# Sheet1.net
KiCad netlist of a schematic drawn in Altium Designer
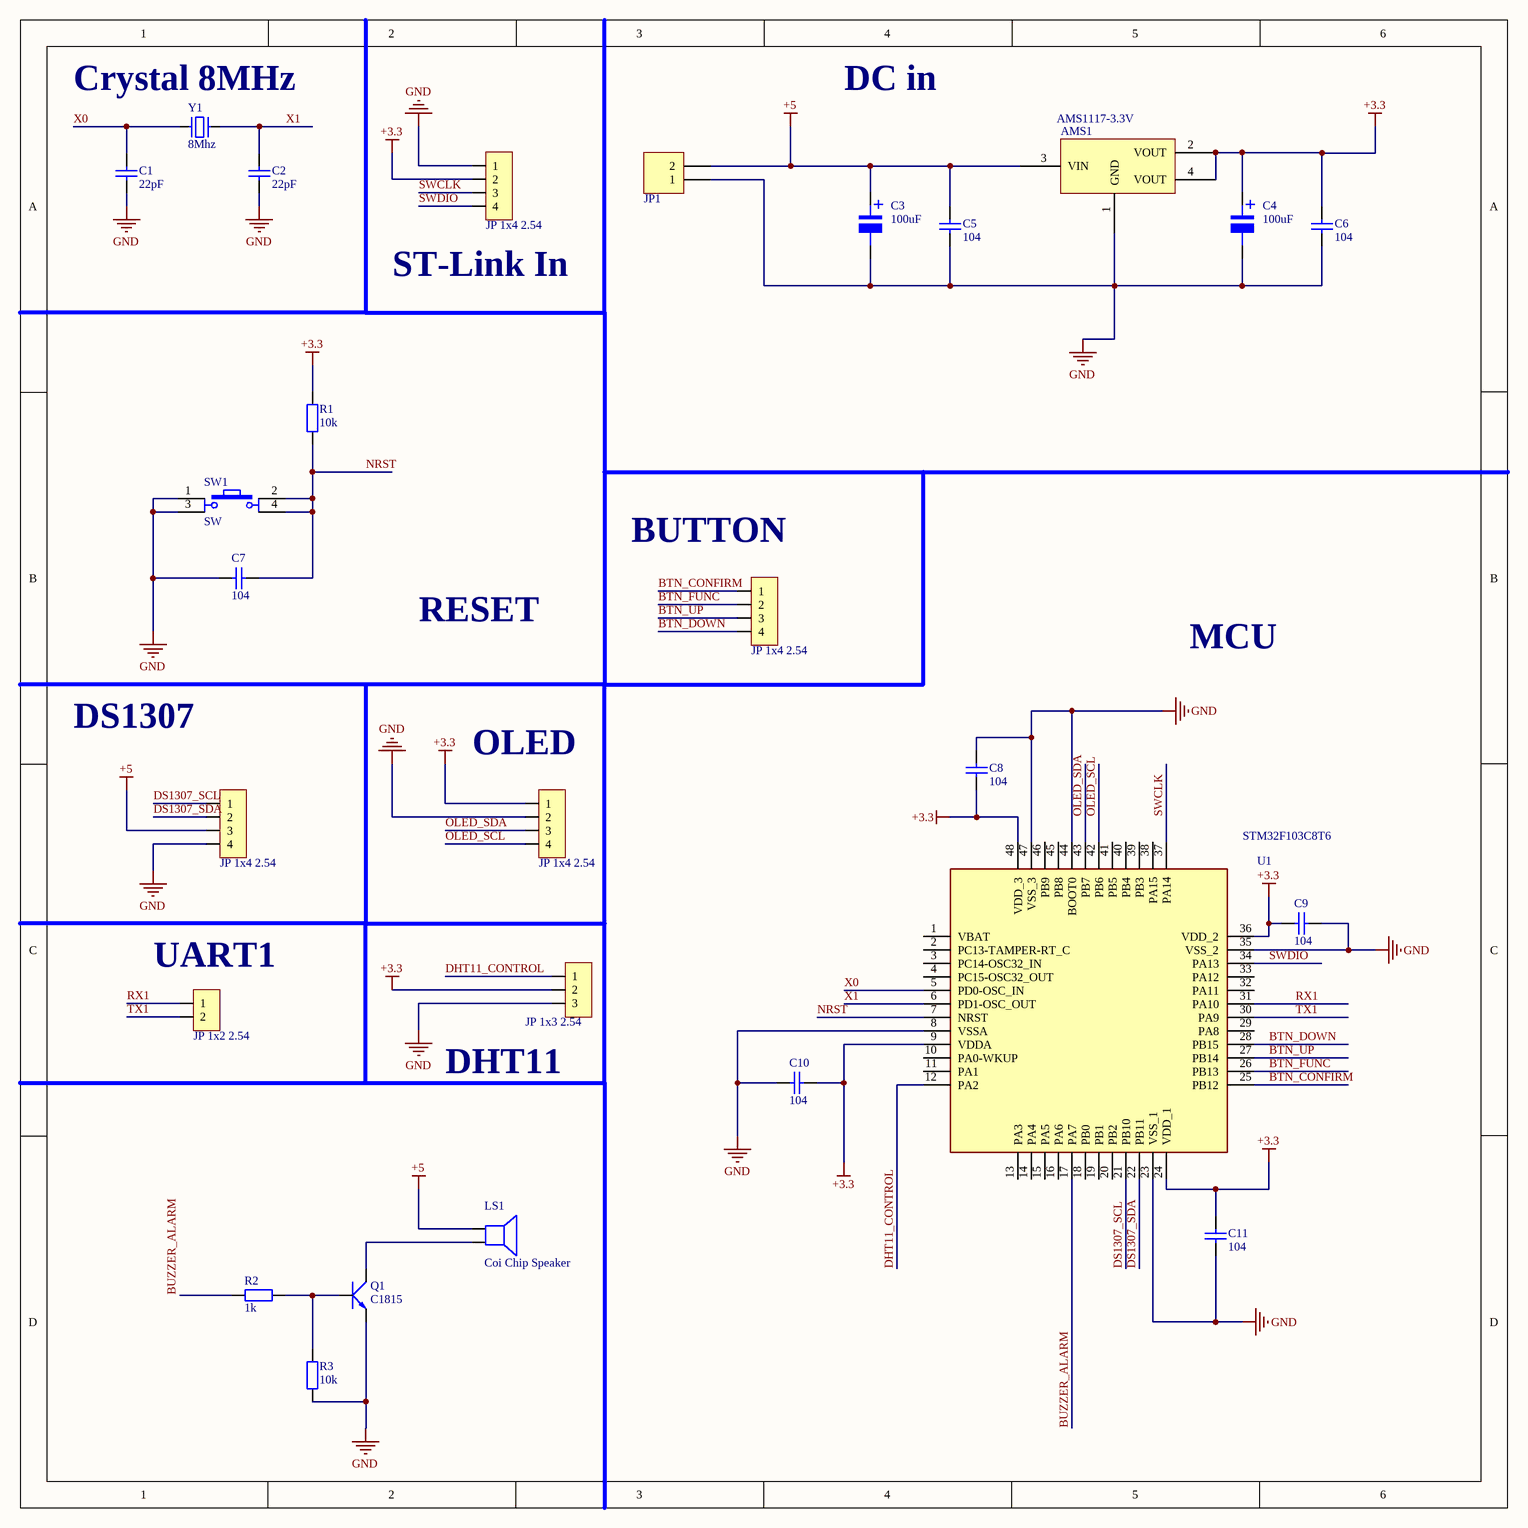
[diagram p0: Sheet1.SchDoc]

(export (version "E")
  (design (tool "Eeschema 10.0.6"))
  (components
    (comp (ref "AMS1")
      (value "AMS1117-3.3V")
      (footprint "SOT223")
      (description "Dán")
      (libsource (lib "Altium_Lib_by_KhueNguyenCreator") (part "AMS1117 SMD"))
    )
    (comp (ref "C1")
      (value "22pF")
      (footprint "tu 1206")
      (description "Dán")
      (libsource (lib "Altium_Lib_by_KhueNguyenCreator") (part "Tu 1206 22pF 50V 10%"))
    )
    (comp (ref "C2")
      (value "22pF")
      (footprint "tu 1206")
      (description "Dán")
      (libsource (lib "Altium_Lib_by_KhueNguyenCreator") (part "Tu 1206 22pF 50V 10%"))
    )
    (comp (ref "C3")
      (value "100uF")
      (footprint "tu nhom 6.3 (d)")
      (description "Dán")
      (libsource (lib "Altium_Lib_by_KhueNguyenCreator") (part "Tu Nhom 100uF 16V"))
    )
    (comp (ref "C4")
      (value "100uF")
      (footprint "tu nhom 6.3 (d)")
      (description "Dán")
      (libsource (lib "Altium_Lib_by_KhueNguyenCreator") (part "Tu Nhom 100uF 16V"))
    )
    (comp (ref "C5")
      (value "104")
      (footprint "tu 1206")
      (description "Dán")
      (libsource (lib "Altium_Lib_by_KhueNguyenCreator") (part "Tu 1206 104 50V 20%"))
    )
    (comp (ref "C6")
      (value "104")
      (footprint "tu 1206")
      (description "Dán")
      (libsource (lib "Altium_Lib_by_KhueNguyenCreator") (part "Tu 1206 104 50V 20%"))
    )
    (comp (ref "C7")
      (value "104")
      (footprint "tu 1206")
      (description "Dán")
      (libsource (lib "Altium_Lib_by_KhueNguyenCreator") (part "Tu 1206 104 50V 20%"))
    )
    (comp (ref "C8")
      (value "104")
      (footprint "tu 1206")
      (description "Dán")
      (libsource (lib "Altium_Lib_by_KhueNguyenCreator") (part "Tu 1206 104 50V 20%"))
    )
    (comp (ref "C9")
      (value "104")
      (footprint "tu 1206")
      (description "Dán")
      (libsource (lib "Altium_Lib_by_KhueNguyenCreator") (part "Tu 1206 104 50V 20%"))
    )
    (comp (ref "C10")
      (value "104")
      (footprint "tu 1206")
      (description "Dán")
      (libsource (lib "Altium_Lib_by_KhueNguyenCreator") (part "Tu 1206 104 50V 20%"))
    )
    (comp (ref "C11")
      (value "104")
      (footprint "tu 1206")
      (description "Dán")
      (libsource (lib "Altium_Lib_by_KhueNguyenCreator") (part "Tu 1206 104 50V 20%"))
    )
    (comp (ref "JP1")
      (value "Header 2_1")
      (footprint "HED2")
      (description "Header, 2-Pin")
      (fields (field (name "MANUFACTURER") "Generic Components"))
      (libsource (lib "syhaunguyen") (part "Header 2_1"))
    )
    (comp (ref "JP2")
      (value "JP 1x4 2.54")
      (footprint "JP 1x4 DT")
      (description "Cắm")
      (libsource (lib "Altium_Lib_by_KhueNguyenCreator") (part "JP 1x4 2.54 Duc Thang"))
    )
    (comp (ref "JP3")
      (value "JP 1x4 2.54")
      (footprint "JP 1x4 DT")
      (description "Cắm")
      (libsource (lib "Altium_Lib_by_KhueNguyenCreator") (part "JP 1x4 2.54 Duc Thang"))
    )
    (comp (ref "JP4")
      (value "JP 1x4 2.54")
      (footprint "JP 1x4 DT")
      (description "Cắm")
      (libsource (lib "Altium_Lib_by_KhueNguyenCreator") (part "JP 1x4 2.54 Duc Thang"))
    )
    (comp (ref "JP5")
      (value "JP 1x4 2.54")
      (footprint "JP 1x4 DT")
      (description "Cắm")
      (libsource (lib "Altium_Lib_by_KhueNguyenCreator") (part "JP 1x4 2.54 Duc Thang"))
    )
    (comp (ref "JP6")
      (value "JP 1x3 2.54")
      (footprint "JP 1x3 DT")
      (description "Cắm")
      (libsource (lib "Altium_Lib_by_KhueNguyenCreator") (part "JP 1x3 2.54 Duc Thang"))
    )
    (comp (ref "JP7")
      (value "JP 1x2 2.54")
      (footprint "JP 1x2 DT")
      (description "Cắm")
      (libsource (lib "Altium_Lib_by_KhueNguyenCreator") (part "JP 1x2 2.54 Duc Thang"))
    )
    (comp (ref "LS1")
      (value "Coi Chip Speaker")
      (footprint "Coi Chip Speacker")
      (description "Còi chip")
      (libsource (lib "Altium_Lib_by_KhueNguyenCreator") (part "Coi Chip Speaker"))
    )
    (comp (ref "Q1")
      (value "C1815")
      (footprint "TO92")
      (description "NPN transistor")
      (libsource (lib "Altium_Lib_by_KhueNguyenCreator") (part "Trans C1815 DIP"))
    )
    (comp (ref "R1")
      (value "10k")
      (footprint "tro smd 1206")
      (description "Dán")
      (libsource (lib "Altium_Lib_by_KhueNguyenCreator") (part "Tro 1206 1% 10k"))
    )
    (comp (ref "R2")
      (value "1k")
      (footprint "tro smd 1206")
      (description "Dán")
      (libsource (lib "Altium_Lib_by_KhueNguyenCreator") (part "Tro 1206 1% 1k"))
    )
    (comp (ref "R3")
      (value "10k")
      (footprint "tro smd 1206")
      (description "Dán")
      (libsource (lib "Altium_Lib_by_KhueNguyenCreator") (part "Tro 1206 1% 10k"))
    )
    (comp (ref "SW1")
      (value "SW")
      (footprint "SW4")
      (description "Switch button 4 pin")
      (libsource (lib "syhaunguyen") (part "SW4"))
    )
    (comp (ref "U1")
      (value "STM32F103C8T6")
      (footprint "LQFP-48_19.6_393_58X11_SMD")
      (description "ARM® Cortex®-M3 STM32F1 Microcontroller IC 32-Bit 72MHz 64KB (64K x 8) FLASH 48-LQFP (7x7)")
      (fields (field (name "MANUFACTURER") "STMicroelectronics"))
      (libsource (lib "Altium_Lib_by_KhueNguyenCreator") (part "IC_STM32F103C8T6"))
    )
    (comp (ref "Y1")
      (value "8Mhz")
      (footprint "Thach Anh 2 chan SMD")
      (description "Crystal For all Crystal 2pin.")
      (libsource (lib "Altium_Lib_by_KhueNguyenCreator") (part "Thach Anh 2 chan SMD"))
    )
  )
  (nets
    (net (code "1") (name "+3.3") (class "Default")
      (node (ref "AMS1") (pin "2") (pinfunction "VOUT_2") (pintype "passive"))
      (node (ref "AMS1") (pin "4") (pinfunction "VOUT_4") (pintype "passive"))
      (node (ref "C10") (pin "1") (pinfunction "1_1") (pintype "passive"))
      (node (ref "C11") (pin "1") (pinfunction "1_1") (pintype "passive"))
      (node (ref "C4") (pin "1") (pinfunction "1_1") (pintype "passive"))
      (node (ref "C6") (pin "1") (pinfunction "1_1") (pintype "passive"))
      (node (ref "C8") (pin "2") (pinfunction "2_2") (pintype "passive"))
      (node (ref "C9") (pin "2") (pinfunction "2_2") (pintype "passive"))
      (node (ref "JP2") (pin "2") (pinfunction "2_2") (pintype "passive"))
      (node (ref "JP5") (pin "1") (pinfunction "1_1") (pintype "passive"))
      (node (ref "JP6") (pin "2") (pinfunction "2_2") (pintype "passive"))
      (node (ref "R1") (pin "2") (pinfunction "2_2") (pintype "passive"))
      (node (ref "U1") (pin "24") (pinfunction "VDD_1_24") (pintype "passive"))
      (node (ref "U1") (pin "36") (pinfunction "VDD_2_36") (pintype "passive"))
      (node (ref "U1") (pin "48") (pinfunction "VDD_3_48") (pintype "passive"))
      (node (ref "U1") (pin "9") (pinfunction "VDDA_9") (pintype "passive"))
    )
    (net (code "2") (name "+5") (class "Default")
      (node (ref "AMS1") (pin "3") (pinfunction "VIN_3") (pintype "passive"))
      (node (ref "C3") (pin "1") (pinfunction "1_1") (pintype "passive"))
      (node (ref "C5") (pin "1") (pinfunction "1_1") (pintype "passive"))
      (node (ref "JP1") (pin "2") (pinfunction "2_2") (pintype "passive"))
      (node (ref "JP4") (pin "3") (pinfunction "3_3") (pintype "passive"))
      (node (ref "LS1") (pin "1") (pinfunction "1_1") (pintype "passive"))
    )
    (net (code "3") (name "/BTN_CONFIRM") (class "Default")
      (node (ref "JP3") (pin "1") (pinfunction "1_1") (pintype "passive"))
      (node (ref "U1") (pin "25") (pinfunction "PB12_25") (pintype "passive"))
    )
    (net (code "4") (name "/BTN_DOWN") (class "Default")
      (node (ref "JP3") (pin "4") (pinfunction "4_4") (pintype "passive"))
      (node (ref "U1") (pin "28") (pinfunction "PB15_28") (pintype "passive"))
    )
    (net (code "5") (name "/BTN_FUNC") (class "Default")
      (node (ref "JP3") (pin "2") (pinfunction "2_2") (pintype "passive"))
      (node (ref "U1") (pin "26") (pinfunction "PB13_26") (pintype "passive"))
    )
    (net (code "6") (name "/BTN_UP") (class "Default")
      (node (ref "JP3") (pin "3") (pinfunction "3_3") (pintype "passive"))
      (node (ref "U1") (pin "27") (pinfunction "PB14_27") (pintype "passive"))
    )
    (net (code "7") (name "/BUZZER_ALARM") (class "Default")
      (node (ref "R2") (pin "1") (pinfunction "1_1") (pintype "passive"))
      (node (ref "U1") (pin "17") (pinfunction "PA7_17") (pintype "passive"))
    )
    (net (code "8") (name "/DHT11_CONTROL") (class "Default")
      (node (ref "JP6") (pin "1") (pinfunction "1_1") (pintype "passive"))
      (node (ref "U1") (pin "12") (pinfunction "PA2_12") (pintype "passive"))
    )
    (net (code "9") (name "/DS1307_SCL") (class "Default")
      (node (ref "JP4") (pin "1") (pinfunction "1_1") (pintype "passive"))
      (node (ref "U1") (pin "21") (pinfunction "PB10_21") (pintype "passive"))
    )
    (net (code "10") (name "/DS1307_SDA") (class "Default")
      (node (ref "JP4") (pin "2") (pinfunction "2_2") (pintype "passive"))
      (node (ref "U1") (pin "22") (pinfunction "PB11_22") (pintype "passive"))
    )
    (net (code "11") (name "/NRST") (class "Default")
      (node (ref "C7") (pin "2") (pinfunction "2_2") (pintype "passive"))
      (node (ref "R1") (pin "1") (pinfunction "1_1") (pintype "passive"))
      (node (ref "SW1") (pin "2") (pintype "passive"))
      (node (ref "SW1") (pin "4") (pintype "passive"))
      (node (ref "U1") (pin "7") (pinfunction "NRST_7") (pintype "passive"))
    )
    (net (code "12") (name "/OLED_SCL") (class "Default")
      (node (ref "JP5") (pin "4") (pinfunction "4_4") (pintype "passive"))
      (node (ref "U1") (pin "42") (pinfunction "PB6_42") (pintype "passive"))
    )
    (net (code "13") (name "/OLED_SDA") (class "Default")
      (node (ref "JP5") (pin "3") (pinfunction "3_3") (pintype "passive"))
      (node (ref "U1") (pin "43") (pinfunction "PB7_43") (pintype "passive"))
    )
    (net (code "14") (name "/RX1") (class "Default")
      (node (ref "JP7") (pin "1") (pinfunction "1_1") (pintype "passive"))
      (node (ref "U1") (pin "31") (pinfunction "PA10_31") (pintype "passive"))
    )
    (net (code "15") (name "/SWCLK") (class "Default")
      (node (ref "JP2") (pin "3") (pinfunction "3_3") (pintype "passive"))
      (node (ref "U1") (pin "37") (pinfunction "PA14_37") (pintype "passive"))
    )
    (net (code "16") (name "/SWDIO") (class "Default")
      (node (ref "JP2") (pin "4") (pinfunction "4_4") (pintype "passive"))
      (node (ref "U1") (pin "34") (pinfunction "PA13_34") (pintype "passive"))
    )
    (net (code "17") (name "/TX1") (class "Default")
      (node (ref "JP7") (pin "2") (pinfunction "2_2") (pintype "passive"))
      (node (ref "U1") (pin "30") (pinfunction "PA9_30") (pintype "passive"))
    )
    (net (code "18") (name "/X0") (class "Default")
      (node (ref "C1") (pin "1") (pinfunction "1_1") (pintype "passive"))
      (node (ref "U1") (pin "5") (pinfunction "PD0-OSC_IN_5") (pintype "passive"))
      (node (ref "Y1") (pin "1") (pinfunction "1_1") (pintype "passive"))
    )
    (net (code "19") (name "/X1") (class "Default")
      (node (ref "C2") (pin "1") (pinfunction "1_1") (pintype "passive"))
      (node (ref "U1") (pin "6") (pinfunction "PD1-OSC_OUT_6") (pintype "passive"))
      (node (ref "Y1") (pin "2") (pinfunction "2_2") (pintype "passive"))
    )
    (net (code "20") (name "GND") (class "Default")
      (node (ref "AMS1") (pin "1") (pinfunction "GND_1") (pintype "passive"))
      (node (ref "C1") (pin "2") (pinfunction "2_2") (pintype "passive"))
      (node (ref "C10") (pin "2") (pinfunction "2_2") (pintype "passive"))
      (node (ref "C11") (pin "2") (pinfunction "2_2") (pintype "passive"))
      (node (ref "C2") (pin "2") (pinfunction "2_2") (pintype "passive"))
      (node (ref "C3") (pin "2") (pinfunction "2_2") (pintype "passive"))
      (node (ref "C4") (pin "2") (pinfunction "2_2") (pintype "passive"))
      (node (ref "C5") (pin "2") (pinfunction "2_2") (pintype "passive"))
      (node (ref "C6") (pin "2") (pinfunction "2_2") (pintype "passive"))
      (node (ref "C7") (pin "1") (pinfunction "1_1") (pintype "passive"))
      (node (ref "C8") (pin "1") (pinfunction "1_1") (pintype "passive"))
      (node (ref "C9") (pin "1") (pinfunction "1_1") (pintype "passive"))
      (node (ref "JP1") (pin "1") (pinfunction "1_1") (pintype "passive"))
      (node (ref "JP2") (pin "1") (pinfunction "1_1") (pintype "passive"))
      (node (ref "JP4") (pin "4") (pinfunction "4_4") (pintype "passive"))
      (node (ref "JP5") (pin "2") (pinfunction "2_2") (pintype "passive"))
      (node (ref "JP6") (pin "3") (pinfunction "3_3") (pintype "passive"))
      (node (ref "Q1") (pin "1") (pinfunction "E_1") (pintype "passive"))
      (node (ref "R3") (pin "1") (pinfunction "1_1") (pintype "passive"))
      (node (ref "SW1") (pin "1") (pintype "passive"))
      (node (ref "SW1") (pin "3") (pintype "passive"))
      (node (ref "U1") (pin "23") (pinfunction "VSS_1_23") (pintype "passive"))
      (node (ref "U1") (pin "35") (pinfunction "VSS_2_35") (pintype "passive"))
      (node (ref "U1") (pin "44") (pinfunction "BOOT0_44") (pintype "passive"))
      (node (ref "U1") (pin "47") (pinfunction "VSS_3_47") (pintype "passive"))
      (node (ref "U1") (pin "8") (pinfunction "VSSA_8") (pintype "passive"))
    )
    (net (code "21") (name "Net-(Q1-B)") (class "Default")
      (node (ref "Q1") (pin "3") (pinfunction "B_3") (pintype "passive"))
      (node (ref "R2") (pin "2") (pinfunction "2_2") (pintype "passive"))
      (node (ref "R3") (pin "2") (pinfunction "2_2") (pintype "passive"))
    )
    (net (code "22") (name "Net-(Q1-C)") (class "Default")
      (node (ref "LS1") (pin "2") (pinfunction "2_2") (pintype "passive"))
      (node (ref "Q1") (pin "2") (pinfunction "C_2") (pintype "passive"))
    )
    (net (code "23") (name "unconnected-(U1-PA0-WKUP-Pad10)") (class "Default")
      (node (ref "U1") (pin "10") (pinfunction "PA0-WKUP_10") (pintype "passive"))
    )
    (net (code "24") (name "unconnected-(U1-PA1-Pad11)") (class "Default")
      (node (ref "U1") (pin "11") (pinfunction "PA1_11") (pintype "passive"))
    )
    (net (code "25") (name "unconnected-(U1-PA3-Pad13)") (class "Default")
      (node (ref "U1") (pin "13") (pinfunction "PA3_13") (pintype "passive"))
    )
    (net (code "26") (name "unconnected-(U1-PA4-Pad14)") (class "Default")
      (node (ref "U1") (pin "14") (pinfunction "PA4_14") (pintype "passive"))
    )
    (net (code "27") (name "unconnected-(U1-PA5-Pad15)") (class "Default")
      (node (ref "U1") (pin "15") (pinfunction "PA5_15") (pintype "passive"))
    )
    (net (code "28") (name "unconnected-(U1-PA6-Pad16)") (class "Default")
      (node (ref "U1") (pin "16") (pinfunction "PA6_16") (pintype "passive"))
    )
    (net (code "29") (name "unconnected-(U1-PA8-Pad29)") (class "Default")
      (node (ref "U1") (pin "29") (pinfunction "PA8_29") (pintype "passive"))
    )
    (net (code "30") (name "unconnected-(U1-PA11-Pad32)") (class "Default")
      (node (ref "U1") (pin "32") (pinfunction "PA11_32") (pintype "passive"))
    )
    (net (code "31") (name "unconnected-(U1-PA12-Pad33)") (class "Default")
      (node (ref "U1") (pin "33") (pinfunction "PA12_33") (pintype "passive"))
    )
    (net (code "32") (name "unconnected-(U1-PA15-Pad38)") (class "Default")
      (node (ref "U1") (pin "38") (pinfunction "PA15_38") (pintype "passive"))
    )
    (net (code "33") (name "unconnected-(U1-PB0-Pad18)") (class "Default")
      (node (ref "U1") (pin "18") (pinfunction "PB0_18") (pintype "passive"))
    )
    (net (code "34") (name "unconnected-(U1-PB1-Pad19)") (class "Default")
      (node (ref "U1") (pin "19") (pinfunction "PB1_19") (pintype "passive"))
    )
    (net (code "35") (name "unconnected-(U1-PB2-Pad20)") (class "Default")
      (node (ref "U1") (pin "20") (pinfunction "PB2_20") (pintype "passive"))
    )
    (net (code "36") (name "unconnected-(U1-PB3-Pad39)") (class "Default")
      (node (ref "U1") (pin "39") (pinfunction "PB3_39") (pintype "passive"))
    )
    (net (code "37") (name "unconnected-(U1-PB4-Pad40)") (class "Default")
      (node (ref "U1") (pin "40") (pinfunction "PB4_40") (pintype "passive"))
    )
    (net (code "38") (name "unconnected-(U1-PB5-Pad41)") (class "Default")
      (node (ref "U1") (pin "41") (pinfunction "PB5_41") (pintype "passive"))
    )
    (net (code "39") (name "unconnected-(U1-PB8-Pad45)") (class "Default")
      (node (ref "U1") (pin "45") (pinfunction "PB8_45") (pintype "passive"))
    )
    (net (code "40") (name "unconnected-(U1-PB9-Pad46)") (class "Default")
      (node (ref "U1") (pin "46") (pinfunction "PB9_46") (pintype "passive"))
    )
    (net (code "41") (name "unconnected-(U1-PC13-TAMPER-RT_C-Pad2)") (class "Default")
      (node (ref "U1") (pin "2") (pinfunction "PC13-TAMPER-RT_C_2") (pintype "passive"))
    )
    (net (code "42") (name "unconnected-(U1-PC14-OSC32_IN-Pad3)") (class "Default")
      (node (ref "U1") (pin "3") (pinfunction "PC14-OSC32_IN_3") (pintype "passive"))
    )
    (net (code "43") (name "unconnected-(U1-PC15-OSC32_OUT-Pad4)") (class "Default")
      (node (ref "U1") (pin "4") (pinfunction "PC15-OSC32_OUT_4") (pintype "passive"))
    )
    (net (code "44") (name "unconnected-(U1-VBAT-Pad1)") (class "Default")
      (node (ref "U1") (pin "1") (pinfunction "VBAT_1") (pintype "passive"))
    )
  )
)
